# pagosaWifi_v1.net
KiCad netlist of a schematic drawn in EAGLE
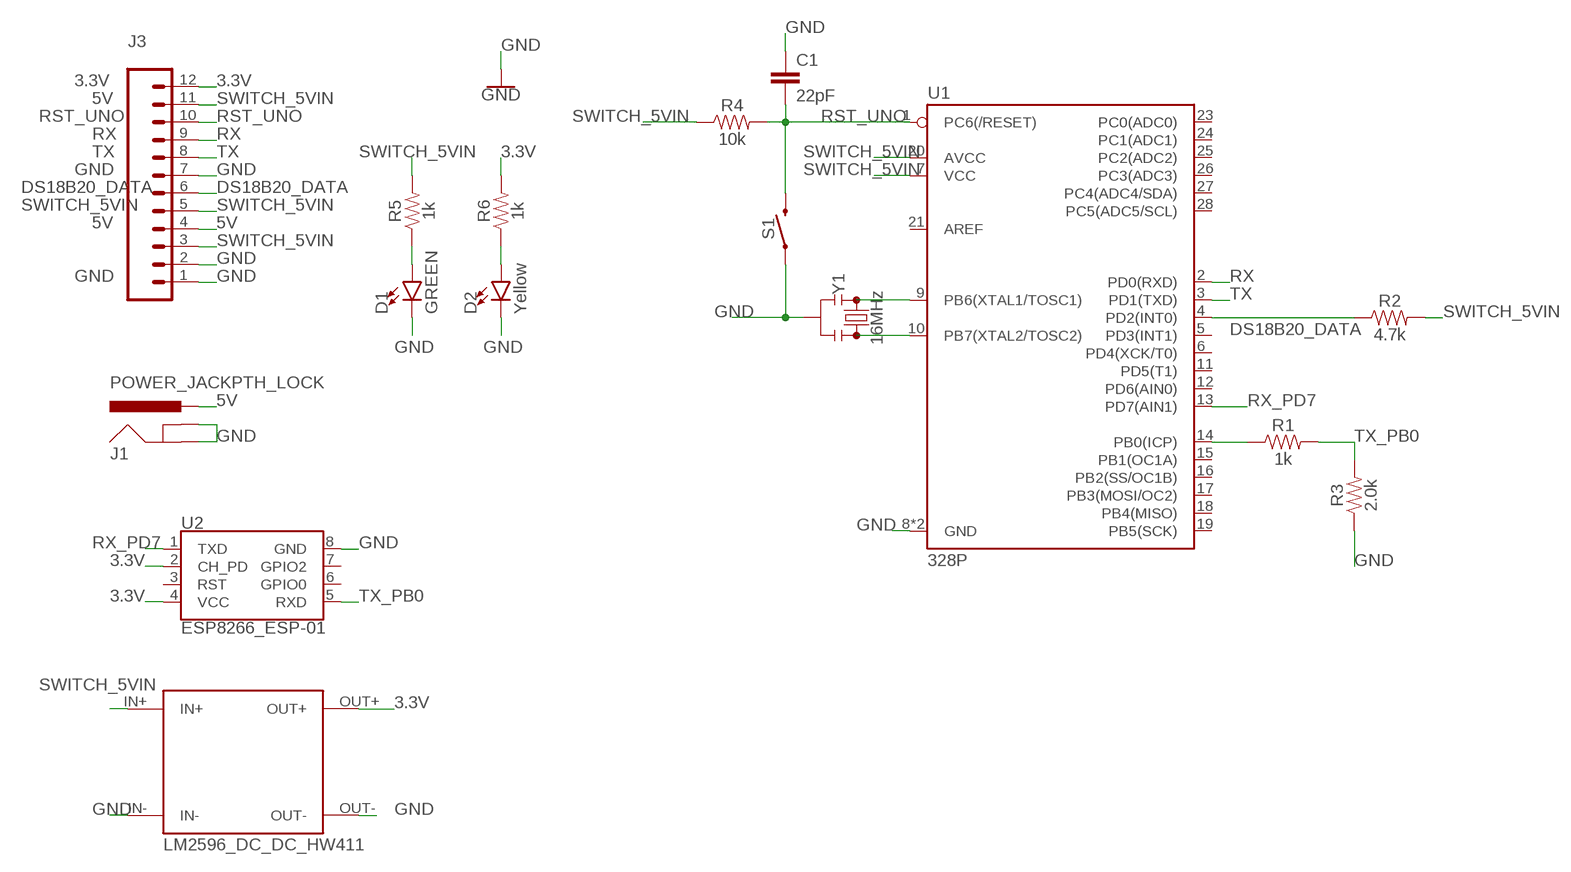
[diagram p0: schematic, sheet 1]

(export (version "E")
  (design (tool "Eeschema 10.0.6"))
  (components
    (comp (ref "C1")
      (value "22pF")
      (footprint "eagle-import:0603")
      (libsource (lib "eagle-import") (part "22PF-0603-50V-5%"))
    )
    (comp (ref "D1")
      (value "GREEN")
      (footprint "eagle-import:LED-0603")
      (libsource (lib "eagle-import") (part "LED-GREEN0603"))
    )
    (comp (ref "D2")
      (value "Yellow")
      (footprint "eagle-import:LED-0603")
      (libsource (lib "eagle-import") (part "LED-YELLOW0603"))
    )
    (comp (ref "J1")
      (value "POWER_JACKPTH_LOCK")
      (footprint "eagle-import:POWER_JACK_PTH_LOCK")
      (libsource (lib "eagle-import") (part "POWER_JACKPTH_LOCK"))
    )
    (comp (ref "J3")
      (value "CONN_12")
      (footprint "eagle-import:1X12")
      (libsource (lib "eagle-import") (part "CONN_12"))
    )
    (comp (ref "R1")
      (value "1k")
      (footprint "eagle-import:0603")
      (libsource (lib "eagle-import") (part "1KOHM-0603-1/10W-1%"))
    )
    (comp (ref "R2")
      (value "4.7k")
      (footprint "eagle-import:0603")
      (libsource (lib "eagle-import") (part "4.7KOHM-0603-1/10W-1%"))
    )
    (comp (ref "R3")
      (value "2.0k")
      (footprint "eagle-import:0603")
      (libsource (lib "eagle-import") (part "2.0KOHM-0603-1/10W-5%"))
    )
    (comp (ref "R4")
      (value "10k")
      (footprint "eagle-import:0603")
      (libsource (lib "eagle-import") (part "10KOHM-0603-1/10W-1%"))
    )
    (comp (ref "R5")
      (value "1k")
      (footprint "eagle-import:0603")
      (libsource (lib "eagle-import") (part "1KOHM-0603-1/10W-1%"))
    )
    (comp (ref "R6")
      (value "1k")
      (footprint "eagle-import:0603")
      (libsource (lib "eagle-import") (part "1KOHM-0603-1/10W-1%"))
    )
    (comp (ref "S1")
      (value "MOMENTARY-SWITCH-SPST-PTH-6.0MM")
      (footprint "eagle-import:TACTILE_SWITCH_PTH_6.0MM")
      (libsource (lib "eagle-import") (part "MOMENTARY-SWITCH-SPST-PTH-6.0MM"))
    )
    (comp (ref "U$1")
      (value "LM2596_DC_DC_HW411")
      (footprint "eagle-import:LM2596_DC_DC_HW411")
      (libsource (lib "eagle-import") (part "LM2596_DC_DC_HW411"))
    )
    (comp (ref "U1")
      (value "328P")
      (footprint "eagle-import:DIP28")
      (libsource (lib "eagle-import") (part "ATMEGA328P_PDIP"))
    )
    (comp (ref "U2")
      (value "ESP8266_ESP-01")
      (footprint "eagle-import:ESP8266_ESP-01")
      (libsource (lib "eagle-import") (part "ESP8266_ESP-01"))
    )
    (comp (ref "Y1")
      (value "16MHz")
      (footprint "eagle-import:RESONATOR-SMD-3.2X1.3")
      (fields (field (name "SPICEPREFIX") "Y"))
      (libsource (lib "eagle-import") (part "RESONATOR-16MHZSMD_3.2X1.3"))
    )
  )
  (nets
    (net (code "1") (name "/3.3V") (class "Default")
      (node (ref "J3") (pin "12") (pinfunction "12_12") (pintype "passive"))
      (node (ref "R6") (pin "2") (pinfunction "2_2") (pintype "passive"))
      (node (ref "U$1") (pin "OUT+") (pinfunction "OUT+_OUT+") (pintype "bidirectional"))
      (node (ref "U2") (pin "2") (pinfunction "CH_PD_2") (pintype "bidirectional"))
      (node (ref "U2") (pin "4") (pinfunction "VCC_4") (pintype "bidirectional"))
    )
    (net (code "2") (name "/5V") (class "Default")
      (node (ref "J1") (pin "PWR") (pinfunction "PWR_PWR") (pintype "bidirectional"))
      (node (ref "J3") (pin "4") (pinfunction "4_4") (pintype "passive"))
    )
    (net (code "3") (name "/DS18B20_DATA") (class "Default")
      (node (ref "J3") (pin "6") (pinfunction "6_6") (pintype "passive"))
      (node (ref "R2") (pin "1") (pinfunction "1_1") (pintype "passive"))
      (node (ref "U1") (pin "4") (pinfunction "PD2(INT0)_4") (pintype "bidirectional"))
    )
    (net (code "4") (name "/RST_UNO") (class "Default")
      (node (ref "C1") (pin "2") (pinfunction "2_2") (pintype "passive"))
      (node (ref "J3") (pin "10") (pinfunction "10_10") (pintype "passive"))
      (node (ref "R4") (pin "2") (pinfunction "2_2") (pintype "passive"))
      (node (ref "S1") (pin "3") (pinfunction "2_3") (pintype "passive"))
      (node (ref "U1") (pin "1") (pinfunction "PC6(/RESET)_1") (pintype "bidirectional"))
    )
    (net (code "5") (name "/RX") (class "Default")
      (node (ref "J3") (pin "9") (pinfunction "9_9") (pintype "passive"))
      (node (ref "U1") (pin "2") (pinfunction "PD0(RXD)_2") (pintype "bidirectional"))
    )
    (net (code "6") (name "/RX_PD7") (class "Default")
      (node (ref "U1") (pin "13") (pinfunction "PD7(AIN1)_13") (pintype "bidirectional"))
      (node (ref "U2") (pin "1") (pinfunction "TXD_1") (pintype "bidirectional"))
    )
    (net (code "7") (name "/SWITCH_5VIN") (class "Default")
      (node (ref "J3") (pin "11") (pinfunction "11_11") (pintype "passive"))
      (node (ref "J3") (pin "3") (pinfunction "3_3") (pintype "passive"))
      (node (ref "J3") (pin "5") (pinfunction "5_5") (pintype "passive"))
      (node (ref "R2") (pin "2") (pinfunction "2_2") (pintype "passive"))
      (node (ref "R4") (pin "1") (pinfunction "1_1") (pintype "passive"))
      (node (ref "R5") (pin "2") (pinfunction "2_2") (pintype "passive"))
      (node (ref "U$1") (pin "IN+") (pinfunction "IN+_IN+") (pintype "bidirectional"))
      (node (ref "U1") (pin "20") (pinfunction "AVCC_20") (pintype "bidirectional"))
      (node (ref "U1") (pin "7") (pinfunction "VCC_7") (pintype "bidirectional"))
    )
    (net (code "8") (name "/TX") (class "Default")
      (node (ref "J3") (pin "8") (pinfunction "8_8") (pintype "passive"))
      (node (ref "U1") (pin "3") (pinfunction "PD1(TXD)_3") (pintype "bidirectional"))
    )
    (net (code "9") (name "/TX_PB0") (class "Default")
      (node (ref "R1") (pin "2") (pinfunction "2_2") (pintype "passive"))
      (node (ref "R3") (pin "2") (pinfunction "2_2") (pintype "passive"))
      (node (ref "U2") (pin "5") (pinfunction "RXD_5") (pintype "bidirectional"))
    )
    (net (code "10") (name "GND") (class "Default")
      (node (ref "C1") (pin "1") (pinfunction "1_1") (pintype "passive"))
      (node (ref "D1") (pin "C") (pinfunction "C_C") (pintype "passive"))
      (node (ref "D2") (pin "C") (pinfunction "C_C") (pintype "passive"))
      (node (ref "J1") (pin "GND") (pinfunction "GND_GND") (pintype "bidirectional"))
      (node (ref "J1") (pin "GNDBREAK") (pinfunction "GNDBREAK_GNDBREAK") (pintype "bidirectional"))
      (node (ref "J3") (pin "1") (pinfunction "1_1") (pintype "passive"))
      (node (ref "J3") (pin "2") (pinfunction "2_2") (pintype "passive"))
      (node (ref "J3") (pin "7") (pinfunction "7_7") (pintype "passive"))
      (node (ref "R3") (pin "1") (pinfunction "1_1") (pintype "passive"))
      (node (ref "S1") (pin "1") (pinfunction "1_1") (pintype "passive"))
      (node (ref "U$1") (pin "IN-") (pinfunction "IN-_IN-") (pintype "bidirectional"))
      (node (ref "U$1") (pin "OUT-") (pinfunction "OUT-_OUT-") (pintype "bidirectional"))
      (node (ref "U1") (pin "22") (pinfunction "GND_22") (pintype "bidirectional"))
      (node (ref "U1") (pin "8") (pinfunction "GND_8") (pintype "bidirectional"))
      (node (ref "U2") (pin "8") (pinfunction "GND_8") (pintype "bidirectional"))
      (node (ref "Y1") (pin "2") (pinfunction "2_2") (pintype "passive"))
    )
    (net (code "11") (name "Net-(D1-PadA)") (class "Default")
      (node (ref "D1") (pin "A") (pinfunction "A_A") (pintype "passive"))
      (node (ref "R5") (pin "1") (pinfunction "1_1") (pintype "passive"))
    )
    (net (code "12") (name "Net-(D2-PadA)") (class "Default")
      (node (ref "D2") (pin "A") (pinfunction "A_A") (pintype "passive"))
      (node (ref "R6") (pin "1") (pinfunction "1_1") (pintype "passive"))
    )
    (net (code "13") (name "Net-(U1-PB0(ICP))") (class "Default")
      (node (ref "R1") (pin "1") (pinfunction "1_1") (pintype "passive"))
      (node (ref "U1") (pin "14") (pinfunction "PB0(ICP)_14") (pintype "bidirectional"))
    )
    (net (code "14") (name "Net-(U1-PB6(XTAL1{slash}TOSC1))") (class "Default")
      (node (ref "U1") (pin "9") (pinfunction "PB6(XTAL1/TOSC1)_9") (pintype "bidirectional"))
      (node (ref "Y1") (pin "1") (pinfunction "1_1") (pintype "passive"))
    )
    (net (code "15") (name "Net-(U1-PB7(XTAL2{slash}TOSC2))") (class "Default")
      (node (ref "U1") (pin "10") (pinfunction "PB7(XTAL2/TOSC2)_10") (pintype "bidirectional"))
      (node (ref "Y1") (pin "3") (pinfunction "3_3") (pintype "passive"))
    )
    (net (code "16") (name "unconnected-(U1-AREF-Pad21)") (class "Default")
      (node (ref "U1") (pin "21") (pinfunction "AREF_21") (pintype "bidirectional"))
    )
    (net (code "17") (name "unconnected-(U1-PB1(OC1A)-Pad15)") (class "Default")
      (node (ref "U1") (pin "15") (pinfunction "PB1(OC1A)_15") (pintype "bidirectional"))
    )
    (net (code "18") (name "unconnected-(U1-PB2(SS{slash}OC1B)-Pad16)") (class "Default")
      (node (ref "U1") (pin "16") (pinfunction "PB2(SS/OC1B)_16") (pintype "bidirectional"))
    )
    (net (code "19") (name "unconnected-(U1-PB3(MOSI{slash}OC2)-Pad17)") (class "Default")
      (node (ref "U1") (pin "17") (pinfunction "PB3(MOSI/OC2)_17") (pintype "bidirectional"))
    )
    (net (code "20") (name "unconnected-(U1-PB4(MISO)-Pad18)") (class "Default")
      (node (ref "U1") (pin "18") (pinfunction "PB4(MISO)_18") (pintype "bidirectional"))
    )
    (net (code "21") (name "unconnected-(U1-PB5(SCK)-Pad19)") (class "Default")
      (node (ref "U1") (pin "19") (pinfunction "PB5(SCK)_19") (pintype "bidirectional"))
    )
    (net (code "22") (name "unconnected-(U1-PC0(ADC0)-Pad23)") (class "Default")
      (node (ref "U1") (pin "23") (pinfunction "PC0(ADC0)_23") (pintype "bidirectional"))
    )
    (net (code "23") (name "unconnected-(U1-PC1(ADC1)-Pad24)") (class "Default")
      (node (ref "U1") (pin "24") (pinfunction "PC1(ADC1)_24") (pintype "bidirectional"))
    )
    (net (code "24") (name "unconnected-(U1-PC2(ADC2)-Pad25)") (class "Default")
      (node (ref "U1") (pin "25") (pinfunction "PC2(ADC2)_25") (pintype "bidirectional"))
    )
    (net (code "25") (name "unconnected-(U1-PC3(ADC3)-Pad26)") (class "Default")
      (node (ref "U1") (pin "26") (pinfunction "PC3(ADC3)_26") (pintype "bidirectional"))
    )
    (net (code "26") (name "unconnected-(U1-PC4(ADC4{slash}SDA)-Pad27)") (class "Default")
      (node (ref "U1") (pin "27") (pinfunction "PC4(ADC4/SDA)_27") (pintype "bidirectional"))
    )
    (net (code "27") (name "unconnected-(U1-PC5(ADC5{slash}SCL)-Pad28)") (class "Default")
      (node (ref "U1") (pin "28") (pinfunction "PC5(ADC5/SCL)_28") (pintype "bidirectional"))
    )
    (net (code "28") (name "unconnected-(U1-PD3(INT1)-Pad5)") (class "Default")
      (node (ref "U1") (pin "5") (pinfunction "PD3(INT1)_5") (pintype "bidirectional"))
    )
    (net (code "29") (name "unconnected-(U1-PD4(XCK{slash}T0)-Pad6)") (class "Default")
      (node (ref "U1") (pin "6") (pinfunction "PD4(XCK/T0)_6") (pintype "bidirectional"))
    )
    (net (code "30") (name "unconnected-(U1-PD5(T1)-Pad11)") (class "Default")
      (node (ref "U1") (pin "11") (pinfunction "PD5(T1)_11") (pintype "bidirectional"))
    )
    (net (code "31") (name "unconnected-(U1-PD6(AIN0)-Pad12)") (class "Default")
      (node (ref "U1") (pin "12") (pinfunction "PD6(AIN0)_12") (pintype "bidirectional"))
    )
    (net (code "32") (name "unconnected-(U2-GPIO0-Pad6)") (class "Default")
      (node (ref "U2") (pin "6") (pinfunction "GPIO0_6") (pintype "bidirectional"))
    )
    (net (code "33") (name "unconnected-(U2-GPIO2-Pad7)") (class "Default")
      (node (ref "U2") (pin "7") (pinfunction "GPIO2_7") (pintype "bidirectional"))
    )
    (net (code "34") (name "unconnected-(U2-RST-Pad3)") (class "Default")
      (node (ref "U2") (pin "3") (pinfunction "RST_3") (pintype "bidirectional"))
    )
  )
)
